# MRCS-8xDPDT-Relay.net
KiCad netlist of a schematic drawn in EAGLE
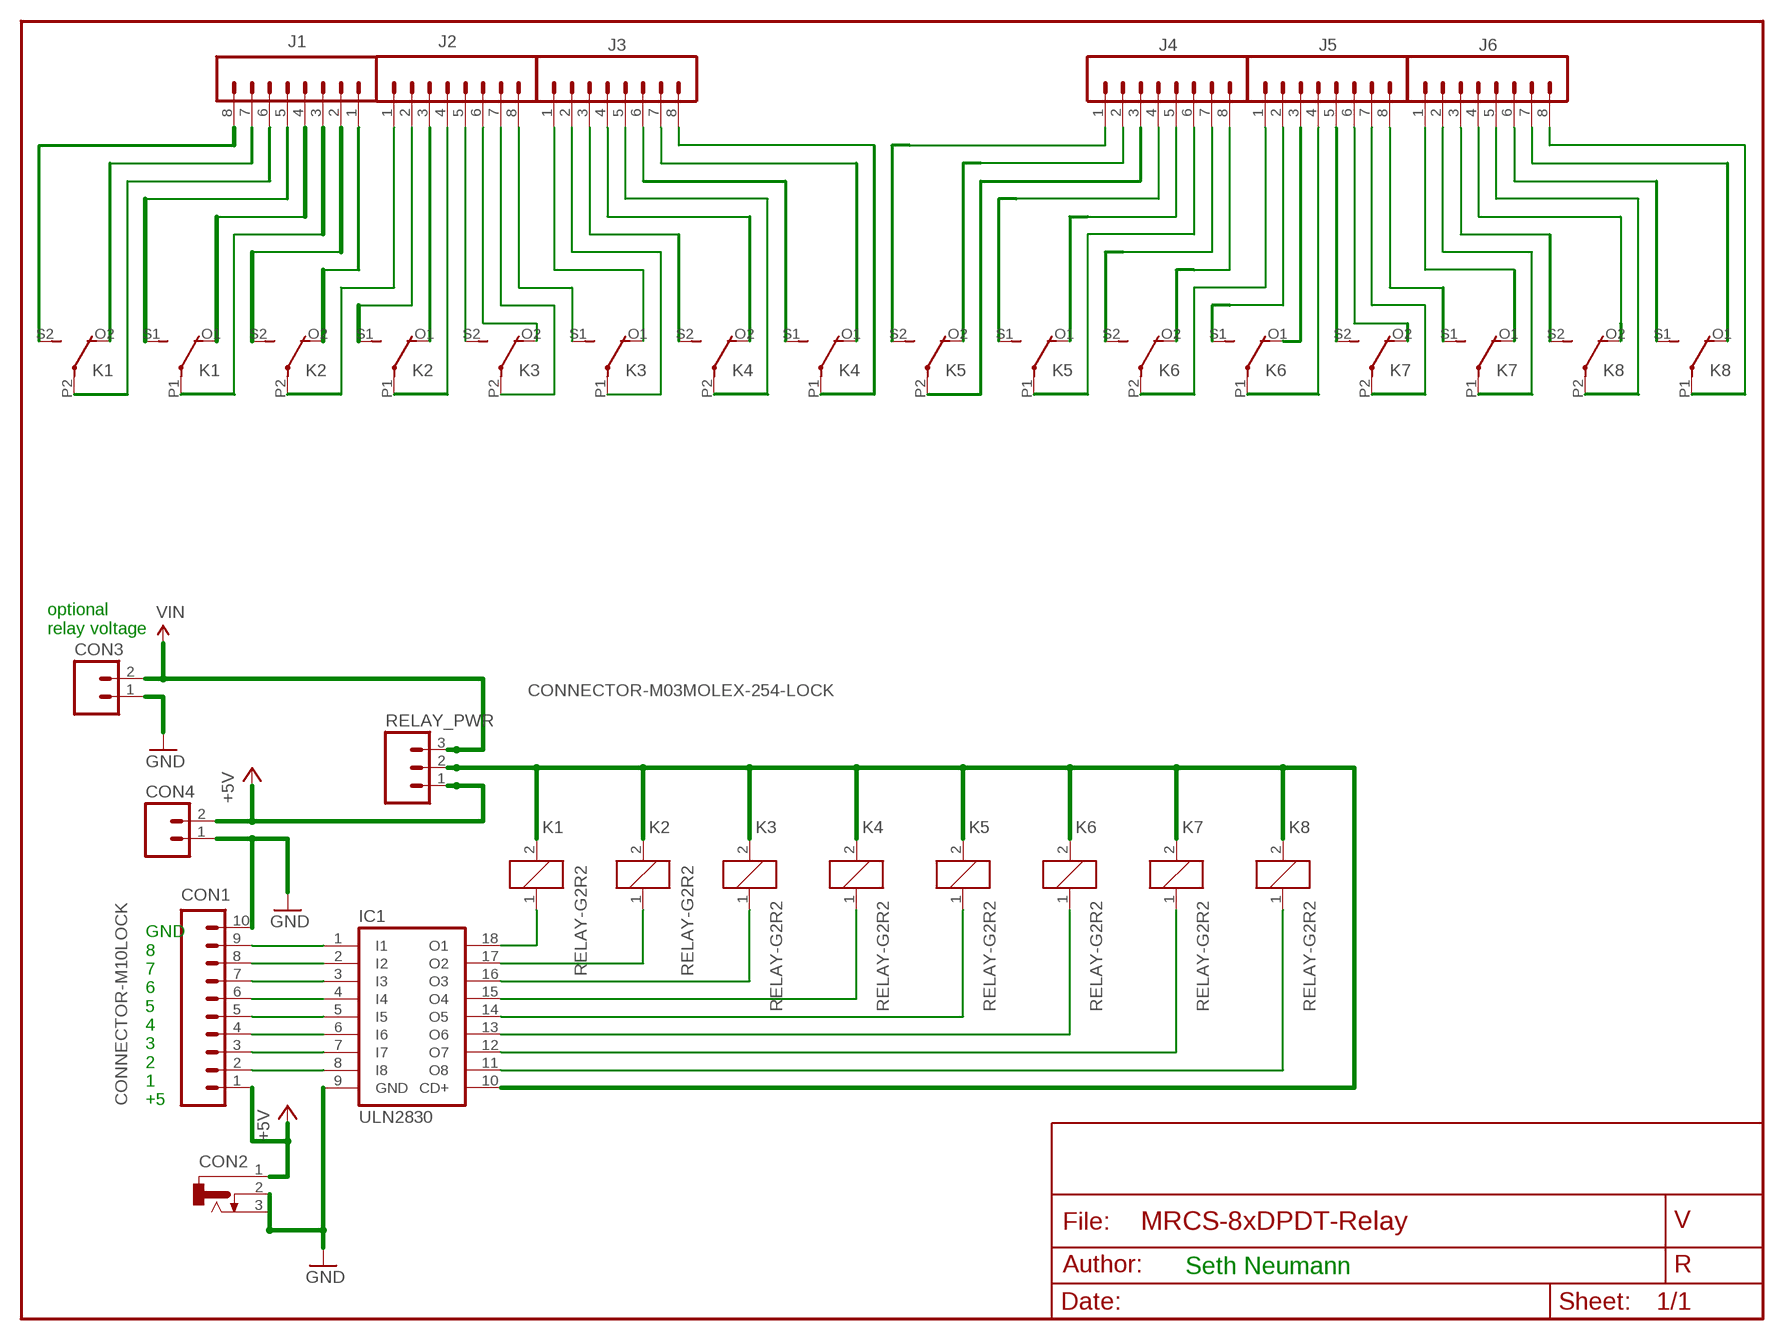
[diagram p0: schematic, sheet 1]

(export (version "E")
  (design (tool "Eeschema 10.0.6"))
  (components
    (comp (ref "CON1")
      (value "CONNECTOR-M10LOCK")
      (footprint "eagle-import:1X10_LOCK")
      (libsource (lib "eagle-import") (part "CONNECTOR-M10LOCK"))
    )
    (comp (ref "CON2")
      (value "CONNECTOR-DC-POWER-RA")
      (footprint "eagle-import:DCJ0202")
      (libsource (lib "eagle-import") (part "CONNECTOR-DC-POWER-RA"))
    )
    (comp (ref "CON3")
      (value "CONNECTOR-M023.5MM-LOCK")
      (footprint "eagle-import:SCREWTERMINAL-3.5MM-2_LOCK")
      (libsource (lib "eagle-import") (part "CONNECTOR-M023.5MM-LOCK"))
    )
    (comp (ref "CON4")
      (value "CONNECTOR-M023.5MM-LOCK")
      (footprint "eagle-import:SCREWTERMINAL-3.5MM-2_LOCK")
      (libsource (lib "eagle-import") (part "CONNECTOR-M023.5MM-LOCK"))
    )
    (comp (ref "IC1")
      (value "ULN2830")
      (footprint "eagle-import:DIL18")
      (libsource (lib "eagle-import") (part "ULN2803A"))
    )
    (comp (ref "J1")
      (value "CONNECTOR-M08LOCK")
      (footprint "eagle-import:1X08_LOCK")
      (libsource (lib "eagle-import") (part "CONNECTOR-M08LOCK"))
    )
    (comp (ref "J2")
      (value "CONNECTOR-M08LOCK")
      (footprint "eagle-import:1X08_LOCK")
      (libsource (lib "eagle-import") (part "CONNECTOR-M08LOCK"))
    )
    (comp (ref "J3")
      (value "CONNECTOR-M08LOCK")
      (footprint "eagle-import:1X08_LOCK")
      (libsource (lib "eagle-import") (part "CONNECTOR-M08LOCK"))
    )
    (comp (ref "J4")
      (value "CONNECTOR-M08LOCK")
      (footprint "eagle-import:1X08_LOCK")
      (libsource (lib "eagle-import") (part "CONNECTOR-M08LOCK"))
    )
    (comp (ref "J5")
      (value "CONNECTOR-M08LOCK")
      (footprint "eagle-import:1X08_LOCK")
      (libsource (lib "eagle-import") (part "CONNECTOR-M08LOCK"))
    )
    (comp (ref "J6")
      (value "CONNECTOR-M08LOCK")
      (footprint "eagle-import:1X08_LOCK")
      (libsource (lib "eagle-import") (part "CONNECTOR-M08LOCK"))
    )
    (comp (ref "K1")
      (value "RELAY-G2R2")
      (footprint "eagle-import:G2R2")
      (fields (field (name "MF") "OMRON COMPONENTS USA") (field (name "MPN") "G2R-2-DC6"))
      (libsource (lib "eagle-import") (part "RELAY-G2R2"))
    )
    (comp (ref "K2")
      (value "RELAY-G2R2")
      (footprint "eagle-import:G2R2")
      (fields (field (name "MF") "OMRON COMPONENTS USA") (field (name "MPN") "G2R-2-DC6"))
      (libsource (lib "eagle-import") (part "RELAY-G2R2"))
    )
    (comp (ref "K3")
      (value "RELAY-G2R2")
      (footprint "eagle-import:G2R2")
      (fields (field (name "MF") "OMRON COMPONENTS USA") (field (name "MPN") "G2R-2-DC6"))
      (libsource (lib "eagle-import") (part "RELAY-G2R2"))
    )
    (comp (ref "K4")
      (value "RELAY-G2R2")
      (footprint "eagle-import:G2R2")
      (fields (field (name "MF") "OMRON COMPONENTS USA") (field (name "MPN") "G2R-2-DC6"))
      (libsource (lib "eagle-import") (part "RELAY-G2R2"))
    )
    (comp (ref "K5")
      (value "RELAY-G2R2")
      (footprint "eagle-import:G2R2")
      (fields (field (name "MF") "OMRON COMPONENTS USA") (field (name "MPN") "G2R-2-DC6"))
      (libsource (lib "eagle-import") (part "RELAY-G2R2"))
    )
    (comp (ref "K6")
      (value "RELAY-G2R2")
      (footprint "eagle-import:G2R2")
      (fields (field (name "MF") "OMRON COMPONENTS USA") (field (name "MPN") "G2R-2-DC6"))
      (libsource (lib "eagle-import") (part "RELAY-G2R2"))
    )
    (comp (ref "K7")
      (value "RELAY-G2R2")
      (footprint "eagle-import:G2R2")
      (fields (field (name "MF") "OMRON COMPONENTS USA") (field (name "MPN") "G2R-2-DC6"))
      (libsource (lib "eagle-import") (part "RELAY-G2R2"))
    )
    (comp (ref "K8")
      (value "RELAY-G2R2")
      (footprint "eagle-import:G2R2")
      (fields (field (name "MF") "OMRON COMPONENTS USA") (field (name "MPN") "G2R-2-DC6"))
      (libsource (lib "eagle-import") (part "RELAY-G2R2"))
    )
    (comp (ref "RELAY_PWR")
      (value "CONNECTOR-M03MOLEX-254-LOCK")
      (footprint "eagle-import:MOLEX-1X3_LOCK")
      (libsource (lib "eagle-import") (part "CONNECTOR-M03MOLEX-254-LOCK"))
    )
  )
  (nets
    (net (code "1") (name "+5V") (class "Default")
      (node (ref "CON1") (pin "1") (pinfunction "1_1") (pintype "passive"))
      (node (ref "CON2") (pin "1") (pinfunction "1_1") (pintype "passive"))
      (node (ref "CON4") (pin "2") (pinfunction "B_2") (pintype "passive"))
      (node (ref "RELAY_PWR") (pin "1") (pinfunction "1_1") (pintype "passive"))
    )
    (net (code "2") (name "GND") (class "Default")
      (node (ref "CON1") (pin "10") (pinfunction "10_10") (pintype "passive"))
      (node (ref "CON2") (pin "2") (pinfunction "2_2") (pintype "passive"))
      (node (ref "CON2") (pin "3") (pinfunction "3_3") (pintype "passive"))
      (node (ref "CON3") (pin "1") (pinfunction "A_1") (pintype "passive"))
      (node (ref "CON4") (pin "1") (pinfunction "A_1") (pintype "passive"))
      (node (ref "IC1") (pin "9") (pinfunction "GND_9") (pintype "power_in"))
    )
    (net (code "3") (name "Net-(IC1-CD+)") (class "Default")
      (node (ref "IC1") (pin "10") (pinfunction "CD+_10") (pintype "passive"))
      (node (ref "K1") (pin "2") (pinfunction "2_2") (pintype "passive"))
      (node (ref "K2") (pin "2") (pinfunction "2_2") (pintype "passive"))
      (node (ref "K3") (pin "2") (pinfunction "2_2") (pintype "passive"))
      (node (ref "K4") (pin "2") (pinfunction "2_2") (pintype "passive"))
      (node (ref "K5") (pin "2") (pinfunction "2_2") (pintype "passive"))
      (node (ref "K6") (pin "2") (pinfunction "2_2") (pintype "passive"))
      (node (ref "K7") (pin "2") (pinfunction "2_2") (pintype "passive"))
      (node (ref "K8") (pin "2") (pinfunction "2_2") (pintype "passive"))
      (node (ref "RELAY_PWR") (pin "2") (pinfunction "2_2") (pintype "passive"))
    )
    (net (code "4") (name "Net-(IC1-I1)") (class "Default")
      (node (ref "CON1") (pin "9") (pinfunction "9_9") (pintype "passive"))
      (node (ref "IC1") (pin "1") (pinfunction "I1_1") (pintype "input"))
    )
    (net (code "5") (name "Net-(IC1-I2)") (class "Default")
      (node (ref "CON1") (pin "8") (pinfunction "8_8") (pintype "passive"))
      (node (ref "IC1") (pin "2") (pinfunction "I2_2") (pintype "input"))
    )
    (net (code "6") (name "Net-(IC1-I3)") (class "Default")
      (node (ref "CON1") (pin "7") (pinfunction "7_7") (pintype "passive"))
      (node (ref "IC1") (pin "3") (pinfunction "I3_3") (pintype "input"))
    )
    (net (code "7") (name "Net-(IC1-I4)") (class "Default")
      (node (ref "CON1") (pin "6") (pinfunction "6_6") (pintype "passive"))
      (node (ref "IC1") (pin "4") (pinfunction "I4_4") (pintype "input"))
    )
    (net (code "8") (name "Net-(IC1-I5)") (class "Default")
      (node (ref "CON1") (pin "5") (pinfunction "5_5") (pintype "passive"))
      (node (ref "IC1") (pin "5") (pinfunction "I5_5") (pintype "input"))
    )
    (net (code "9") (name "Net-(IC1-I6)") (class "Default")
      (node (ref "CON1") (pin "4") (pinfunction "4_4") (pintype "passive"))
      (node (ref "IC1") (pin "6") (pinfunction "I6_6") (pintype "input"))
    )
    (net (code "10") (name "Net-(IC1-I7)") (class "Default")
      (node (ref "CON1") (pin "3") (pinfunction "3_3") (pintype "passive"))
      (node (ref "IC1") (pin "7") (pinfunction "I7_7") (pintype "input"))
    )
    (net (code "11") (name "Net-(IC1-I8)") (class "Default")
      (node (ref "CON1") (pin "2") (pinfunction "2_2") (pintype "passive"))
      (node (ref "IC1") (pin "8") (pinfunction "I8_8") (pintype "input"))
    )
    (net (code "12") (name "Net-(IC1-O1)") (class "Default")
      (node (ref "IC1") (pin "18") (pinfunction "O1_18") (pintype "open_collector"))
      (node (ref "K1") (pin "1") (pinfunction "1_1") (pintype "passive"))
    )
    (net (code "13") (name "Net-(IC1-O2)") (class "Default")
      (node (ref "IC1") (pin "17") (pinfunction "O2_17") (pintype "open_collector"))
      (node (ref "K2") (pin "1") (pinfunction "1_1") (pintype "passive"))
    )
    (net (code "14") (name "Net-(IC1-O3)") (class "Default")
      (node (ref "IC1") (pin "16") (pinfunction "O3_16") (pintype "open_collector"))
      (node (ref "K3") (pin "1") (pinfunction "1_1") (pintype "passive"))
    )
    (net (code "15") (name "Net-(IC1-O4)") (class "Default")
      (node (ref "IC1") (pin "15") (pinfunction "O4_15") (pintype "open_collector"))
      (node (ref "K4") (pin "1") (pinfunction "1_1") (pintype "passive"))
    )
    (net (code "16") (name "Net-(IC1-O5)") (class "Default")
      (node (ref "IC1") (pin "14") (pinfunction "O5_14") (pintype "open_collector"))
      (node (ref "K5") (pin "1") (pinfunction "1_1") (pintype "passive"))
    )
    (net (code "17") (name "Net-(IC1-O6)") (class "Default")
      (node (ref "IC1") (pin "13") (pinfunction "O6_13") (pintype "open_collector"))
      (node (ref "K6") (pin "1") (pinfunction "1_1") (pintype "passive"))
    )
    (net (code "18") (name "Net-(IC1-O7)") (class "Default")
      (node (ref "IC1") (pin "12") (pinfunction "O7_12") (pintype "open_collector"))
      (node (ref "K7") (pin "1") (pinfunction "1_1") (pintype "passive"))
    )
    (net (code "19") (name "Net-(IC1-O8)") (class "Default")
      (node (ref "IC1") (pin "11") (pinfunction "O8_11") (pintype "open_collector"))
      (node (ref "K8") (pin "1") (pinfunction "1_1") (pintype "passive"))
    )
    (net (code "20") (name "Net-(K1B-O)") (class "Default")
      (node (ref "J1") (pin "4") (pinfunction "4_4") (pintype "passive"))
      (node (ref "K1") (pin "O1") (pinfunction "O_O1") (pintype "passive"))
    )
    (net (code "21") (name "Net-(K1B-P)") (class "Default")
      (node (ref "J1") (pin "3") (pinfunction "3_3") (pintype "passive"))
      (node (ref "K1") (pin "P1") (pinfunction "P_P1") (pintype "passive"))
    )
    (net (code "22") (name "Net-(K1B-S)") (class "Default")
      (node (ref "J1") (pin "5") (pinfunction "5_5") (pintype "passive"))
      (node (ref "K1") (pin "S1") (pinfunction "S_S1") (pintype "passive"))
    )
    (net (code "23") (name "Net-(K1C-O)") (class "Default")
      (node (ref "J1") (pin "7") (pinfunction "7_7") (pintype "passive"))
      (node (ref "K1") (pin "O2") (pinfunction "O_O2") (pintype "passive"))
    )
    (net (code "24") (name "Net-(K1C-P)") (class "Default")
      (node (ref "J1") (pin "6") (pinfunction "6_6") (pintype "passive"))
      (node (ref "K1") (pin "P2") (pinfunction "P_P2") (pintype "passive"))
    )
    (net (code "25") (name "Net-(K1C-S)") (class "Default")
      (node (ref "J1") (pin "8") (pinfunction "8_8") (pintype "passive"))
      (node (ref "K1") (pin "S2") (pinfunction "S_S2") (pintype "passive"))
    )
    (net (code "26") (name "Net-(K2B-O)") (class "Default")
      (node (ref "J2") (pin "3") (pinfunction "3_3") (pintype "passive"))
      (node (ref "K2") (pin "O1") (pinfunction "O_O1") (pintype "passive"))
    )
    (net (code "27") (name "Net-(K2B-P)") (class "Default")
      (node (ref "J2") (pin "4") (pinfunction "4_4") (pintype "passive"))
      (node (ref "K2") (pin "P1") (pinfunction "P_P1") (pintype "passive"))
    )
    (net (code "28") (name "Net-(K2B-S)") (class "Default")
      (node (ref "J2") (pin "2") (pinfunction "2_2") (pintype "passive"))
      (node (ref "K2") (pin "S1") (pinfunction "S_S1") (pintype "passive"))
    )
    (net (code "29") (name "Net-(K2C-O)") (class "Default")
      (node (ref "J1") (pin "1") (pinfunction "1_1") (pintype "passive"))
      (node (ref "K2") (pin "O2") (pinfunction "O_O2") (pintype "passive"))
    )
    (net (code "30") (name "Net-(K2C-P)") (class "Default")
      (node (ref "J2") (pin "1") (pinfunction "1_1") (pintype "passive"))
      (node (ref "K2") (pin "P2") (pinfunction "P_P2") (pintype "passive"))
    )
    (net (code "31") (name "Net-(K2C-S)") (class "Default")
      (node (ref "J1") (pin "2") (pinfunction "2_2") (pintype "passive"))
      (node (ref "K2") (pin "S2") (pinfunction "S_S2") (pintype "passive"))
    )
    (net (code "32") (name "Net-(K3B-O)") (class "Default")
      (node (ref "J3") (pin "1") (pinfunction "1_1") (pintype "passive"))
      (node (ref "K3") (pin "O1") (pinfunction "O_O1") (pintype "passive"))
    )
    (net (code "33") (name "Net-(K3B-P)") (class "Default")
      (node (ref "J3") (pin "2") (pinfunction "2_2") (pintype "passive"))
      (node (ref "K3") (pin "P1") (pinfunction "P_P1") (pintype "passive"))
    )
    (net (code "34") (name "Net-(K3B-S)") (class "Default")
      (node (ref "J2") (pin "8") (pinfunction "8_8") (pintype "passive"))
      (node (ref "K3") (pin "S1") (pinfunction "S_S1") (pintype "passive"))
    )
    (net (code "35") (name "Net-(K3C-O)") (class "Default")
      (node (ref "J2") (pin "6") (pinfunction "6_6") (pintype "passive"))
      (node (ref "K3") (pin "O2") (pinfunction "O_O2") (pintype "passive"))
    )
    (net (code "36") (name "Net-(K3C-P)") (class "Default")
      (node (ref "J2") (pin "7") (pinfunction "7_7") (pintype "passive"))
      (node (ref "K3") (pin "P2") (pinfunction "P_P2") (pintype "passive"))
    )
    (net (code "37") (name "Net-(K3C-S)") (class "Default")
      (node (ref "J2") (pin "5") (pinfunction "5_5") (pintype "passive"))
      (node (ref "K3") (pin "S2") (pinfunction "S_S2") (pintype "passive"))
    )
    (net (code "38") (name "Net-(K4B-O)") (class "Default")
      (node (ref "J3") (pin "7") (pinfunction "7_7") (pintype "passive"))
      (node (ref "K4") (pin "O1") (pinfunction "O_O1") (pintype "passive"))
    )
    (net (code "39") (name "Net-(K4B-P)") (class "Default")
      (node (ref "J3") (pin "8") (pinfunction "8_8") (pintype "passive"))
      (node (ref "K4") (pin "P1") (pinfunction "P_P1") (pintype "passive"))
    )
    (net (code "40") (name "Net-(K4B-S)") (class "Default")
      (node (ref "J3") (pin "6") (pinfunction "6_6") (pintype "passive"))
      (node (ref "K4") (pin "S1") (pinfunction "S_S1") (pintype "passive"))
    )
    (net (code "41") (name "Net-(K4C-O)") (class "Default")
      (node (ref "J3") (pin "4") (pinfunction "4_4") (pintype "passive"))
      (node (ref "K4") (pin "O2") (pinfunction "O_O2") (pintype "passive"))
    )
    (net (code "42") (name "Net-(K4C-P)") (class "Default")
      (node (ref "J3") (pin "5") (pinfunction "5_5") (pintype "passive"))
      (node (ref "K4") (pin "P2") (pinfunction "P_P2") (pintype "passive"))
    )
    (net (code "43") (name "Net-(K4C-S)") (class "Default")
      (node (ref "J3") (pin "3") (pinfunction "3_3") (pintype "passive"))
      (node (ref "K4") (pin "S2") (pinfunction "S_S2") (pintype "passive"))
    )
    (net (code "44") (name "Net-(K5B-O)") (class "Default")
      (node (ref "J4") (pin "5") (pinfunction "5_5") (pintype "passive"))
      (node (ref "K5") (pin "O1") (pinfunction "O_O1") (pintype "passive"))
    )
    (net (code "45") (name "Net-(K5B-P)") (class "Default")
      (node (ref "J4") (pin "6") (pinfunction "6_6") (pintype "passive"))
      (node (ref "K5") (pin "P1") (pinfunction "P_P1") (pintype "passive"))
    )
    (net (code "46") (name "Net-(K5B-S)") (class "Default")
      (node (ref "J4") (pin "4") (pinfunction "4_4") (pintype "passive"))
      (node (ref "K5") (pin "S1") (pinfunction "S_S1") (pintype "passive"))
    )
    (net (code "47") (name "Net-(K5C-O)") (class "Default")
      (node (ref "J4") (pin "2") (pinfunction "2_2") (pintype "passive"))
      (node (ref "K5") (pin "O2") (pinfunction "O_O2") (pintype "passive"))
    )
    (net (code "48") (name "Net-(K5C-P)") (class "Default")
      (node (ref "J4") (pin "3") (pinfunction "3_3") (pintype "passive"))
      (node (ref "K5") (pin "P2") (pinfunction "P_P2") (pintype "passive"))
    )
    (net (code "49") (name "Net-(K5C-S)") (class "Default")
      (node (ref "J4") (pin "1") (pinfunction "1_1") (pintype "passive"))
      (node (ref "K5") (pin "S2") (pinfunction "S_S2") (pintype "passive"))
    )
    (net (code "50") (name "Net-(K6B-O)") (class "Default")
      (node (ref "J5") (pin "3") (pinfunction "3_3") (pintype "passive"))
      (node (ref "K6") (pin "O1") (pinfunction "O_O1") (pintype "passive"))
    )
    (net (code "51") (name "Net-(K6B-P)") (class "Default")
      (node (ref "J5") (pin "4") (pinfunction "4_4") (pintype "passive"))
      (node (ref "K6") (pin "P1") (pinfunction "P_P1") (pintype "passive"))
    )
    (net (code "52") (name "Net-(K6B-S)") (class "Default")
      (node (ref "J5") (pin "2") (pinfunction "2_2") (pintype "passive"))
      (node (ref "K6") (pin "S1") (pinfunction "S_S1") (pintype "passive"))
    )
    (net (code "53") (name "Net-(K6C-O)") (class "Default")
      (node (ref "J4") (pin "8") (pinfunction "8_8") (pintype "passive"))
      (node (ref "K6") (pin "O2") (pinfunction "O_O2") (pintype "passive"))
    )
    (net (code "54") (name "Net-(K6C-P)") (class "Default")
      (node (ref "J5") (pin "1") (pinfunction "1_1") (pintype "passive"))
      (node (ref "K6") (pin "P2") (pinfunction "P_P2") (pintype "passive"))
    )
    (net (code "55") (name "Net-(K6C-S)") (class "Default")
      (node (ref "J4") (pin "7") (pinfunction "7_7") (pintype "passive"))
      (node (ref "K6") (pin "S2") (pinfunction "S_S2") (pintype "passive"))
    )
    (net (code "56") (name "Net-(K7B-O)") (class "Default")
      (node (ref "J6") (pin "1") (pinfunction "1_1") (pintype "passive"))
      (node (ref "K7") (pin "O1") (pinfunction "O_O1") (pintype "passive"))
    )
    (net (code "57") (name "Net-(K7B-P)") (class "Default")
      (node (ref "J6") (pin "2") (pinfunction "2_2") (pintype "passive"))
      (node (ref "K7") (pin "P1") (pinfunction "P_P1") (pintype "passive"))
    )
    (net (code "58") (name "Net-(K7B-S)") (class "Default")
      (node (ref "J5") (pin "8") (pinfunction "8_8") (pintype "passive"))
      (node (ref "K7") (pin "S1") (pinfunction "S_S1") (pintype "passive"))
    )
    (net (code "59") (name "Net-(K7C-O)") (class "Default")
      (node (ref "J5") (pin "6") (pinfunction "6_6") (pintype "passive"))
      (node (ref "K7") (pin "O2") (pinfunction "O_O2") (pintype "passive"))
    )
    (net (code "60") (name "Net-(K7C-P)") (class "Default")
      (node (ref "J5") (pin "7") (pinfunction "7_7") (pintype "passive"))
      (node (ref "K7") (pin "P2") (pinfunction "P_P2") (pintype "passive"))
    )
    (net (code "61") (name "Net-(K7C-S)") (class "Default")
      (node (ref "J5") (pin "5") (pinfunction "5_5") (pintype "passive"))
      (node (ref "K7") (pin "S2") (pinfunction "S_S2") (pintype "passive"))
    )
    (net (code "62") (name "Net-(K8B-O)") (class "Default")
      (node (ref "J6") (pin "7") (pinfunction "7_7") (pintype "passive"))
      (node (ref "K8") (pin "O1") (pinfunction "O_O1") (pintype "passive"))
    )
    (net (code "63") (name "Net-(K8B-P)") (class "Default")
      (node (ref "J6") (pin "8") (pinfunction "8_8") (pintype "passive"))
      (node (ref "K8") (pin "P1") (pinfunction "P_P1") (pintype "passive"))
    )
    (net (code "64") (name "Net-(K8B-S)") (class "Default")
      (node (ref "J6") (pin "6") (pinfunction "6_6") (pintype "passive"))
      (node (ref "K8") (pin "S1") (pinfunction "S_S1") (pintype "passive"))
    )
    (net (code "65") (name "Net-(K8C-O)") (class "Default")
      (node (ref "J6") (pin "4") (pinfunction "4_4") (pintype "passive"))
      (node (ref "K8") (pin "O2") (pinfunction "O_O2") (pintype "passive"))
    )
    (net (code "66") (name "Net-(K8C-P)") (class "Default")
      (node (ref "J6") (pin "5") (pinfunction "5_5") (pintype "passive"))
      (node (ref "K8") (pin "P2") (pinfunction "P_P2") (pintype "passive"))
    )
    (net (code "67") (name "Net-(K8C-S)") (class "Default")
      (node (ref "J6") (pin "3") (pinfunction "3_3") (pintype "passive"))
      (node (ref "K8") (pin "S2") (pinfunction "S_S2") (pintype "passive"))
    )
    (net (code "68") (name "VIN") (class "Default")
      (node (ref "CON3") (pin "2") (pinfunction "B_2") (pintype "passive"))
      (node (ref "RELAY_PWR") (pin "3") (pinfunction "3_3") (pintype "passive"))
    )
  )
)
